# powersupply.net
KiCad netlist of a schematic drawn in Altium Designer
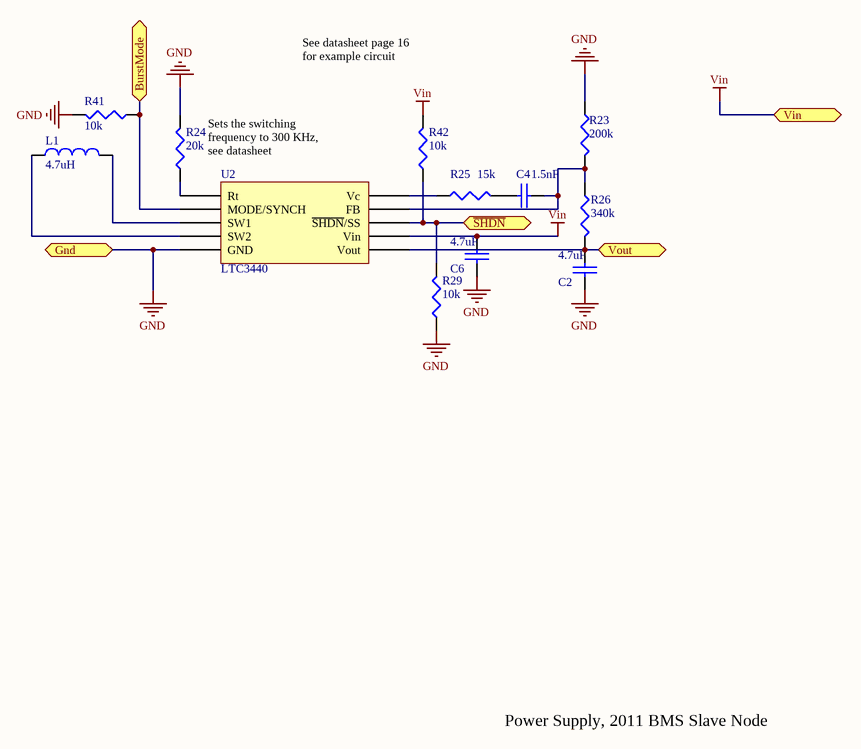
[diagram p0: powersupply.SchDoc]

(export (version "E")
  (design (tool "Eeschema 10.0.6"))
  (components
    (comp (ref "C2")
      (value "4.7uF")
      (footprint "0805")
      (description "Capacitor")
      (libsource (lib "*") (part "CAP"))
    )
    (comp (ref "C4")
      (value "1.5nF")
      (footprint "0603")
      (description "Capacitor")
      (libsource (lib "*") (part "CAP"))
    )
    (comp (ref "C6")
      (value "4.7uF")
      (footprint "0805")
      (description "Capacitor")
      (libsource (lib "*") (part "CAP"))
    )
    (comp (ref "L1")
      (value "4.7uH")
      (footprint "1812")
      (description "Inductor")
      (libsource (lib "Miscellaneous Devices") (part "Inductor"))
    )
    (comp (ref "R23")
      (value "200k")
      (footprint "0603")
      (description "Resistor")
      (libsource (lib "RCLDQ") (part "RES1"))
    )
    (comp (ref "R24")
      (value "20k")
      (footprint "0603")
      (description "Resistor")
      (libsource (lib "RCLDQ") (part "RES1"))
    )
    (comp (ref "R25")
      (value "15k")
      (footprint "0603")
      (description "Resistor")
      (libsource (lib "RCLDQ") (part "RES1"))
    )
    (comp (ref "R26")
      (value "340k")
      (footprint "0603")
      (description "Resistor")
      (libsource (lib "RCLDQ") (part "RES1"))
    )
    (comp (ref "R29")
      (value "10k")
      (footprint "0603")
      (description "Resistor")
      (libsource (lib "RCLDQ") (part "RES1"))
    )
    (comp (ref "R41")
      (value "10k")
      (footprint "0603")
      (description "Resistor")
      (libsource (lib "RCLDQ") (part "RES1"))
    )
    (comp (ref "R42")
      (value "10k")
      (footprint "0603")
      (description "Resistor")
      (libsource (lib "RCLDQ") (part "RES1"))
    )
    (comp (ref "U2") (value "LTC3440") (footprint "MSOP10") (libsource (lib "BMS") (part "LTC3440")))
  )
  (nets
    (net (code "1") (name "/BurstMode") (class "Default")
      (node (ref "R41") (pin "1") (pinfunction "1_1") (pintype "passive"))
      (node (ref "U2") (pin "2") (pinfunction "MODE/SYNCH_2") (pintype "passive"))
    )
    (net (code "2") (name "/Vout") (class "Default")
      (node (ref "C2") (pin "1") (pinfunction "1_1") (pintype "passive"))
      (node (ref "R26") (pin "2") (pinfunction "2_2") (pintype "passive"))
      (node (ref "U2") (pin "6") (pinfunction "Vout_6") (pintype "passive"))
    )
    (net (code "3") (name "/~{SHDN}") (class "Default")
      (node (ref "R29") (pin "2") (pinfunction "2_2") (pintype "passive"))
      (node (ref "R42") (pin "1") (pinfunction "1_1") (pintype "passive"))
      (node (ref "U2") (pin "8") (pinfunction "~{SHDN}/SS_8") (pintype "passive"))
    )
    (net (code "4") (name "GND") (class "Default")
      (node (ref "C2") (pin "2") (pinfunction "2_2") (pintype "passive"))
      (node (ref "C6") (pin "2") (pinfunction "2_2") (pintype "passive"))
      (node (ref "R23") (pin "1") (pinfunction "1_1") (pintype "passive"))
      (node (ref "R24") (pin "2") (pinfunction "2_2") (pintype "passive"))
      (node (ref "R29") (pin "1") (pinfunction "1_1") (pintype "passive"))
      (node (ref "R41") (pin "2") (pinfunction "2_2") (pintype "passive"))
      (node (ref "U2") (pin "5") (pinfunction "GND_5") (pintype "passive"))
    )
    (net (code "5") (name "Net-(C4-Pad1)") (class "Default")
      (node (ref "C4") (pin "1") (pinfunction "1_1") (pintype "passive"))
      (node (ref "R25") (pin "2") (pinfunction "2_2") (pintype "passive"))
    )
    (net (code "6") (name "Net-(U2-FB)") (class "Default")
      (node (ref "C4") (pin "2") (pinfunction "2_2") (pintype "passive"))
      (node (ref "R23") (pin "2") (pinfunction "2_2") (pintype "passive"))
      (node (ref "R26") (pin "1") (pinfunction "1_1") (pintype "passive"))
      (node (ref "U2") (pin "9") (pinfunction "FB_9") (pintype "passive"))
    )
    (net (code "7") (name "Net-(U2-Rt)") (class "Default")
      (node (ref "R24") (pin "1") (pinfunction "1_1") (pintype "passive"))
      (node (ref "U2") (pin "1") (pinfunction "Rt_1") (pintype "passive"))
    )
    (net (code "8") (name "Net-(U2-SW1)") (class "Default")
      (node (ref "L1") (pin "2") (pinfunction "2_2") (pintype "passive"))
      (node (ref "U2") (pin "3") (pinfunction "SW1_3") (pintype "passive"))
    )
    (net (code "9") (name "Net-(U2-SW2)") (class "Default")
      (node (ref "L1") (pin "1") (pinfunction "1_1") (pintype "passive"))
      (node (ref "U2") (pin "4") (pinfunction "SW2_4") (pintype "passive"))
    )
    (net (code "10") (name "Net-(U2-Vc)") (class "Default")
      (node (ref "R25") (pin "1") (pinfunction "1_1") (pintype "passive"))
      (node (ref "U2") (pin "10") (pinfunction "Vc_10") (pintype "passive"))
    )
    (net (code "11") (name "Vin") (class "Default")
      (node (ref "C6") (pin "1") (pinfunction "1_1") (pintype "passive"))
      (node (ref "R42") (pin "2") (pinfunction "2_2") (pintype "passive"))
      (node (ref "U2") (pin "7") (pinfunction "Vin_7") (pintype "passive"))
    )
  )
)
